# sensors.net
KiCad netlist of a schematic drawn in Altium Designer
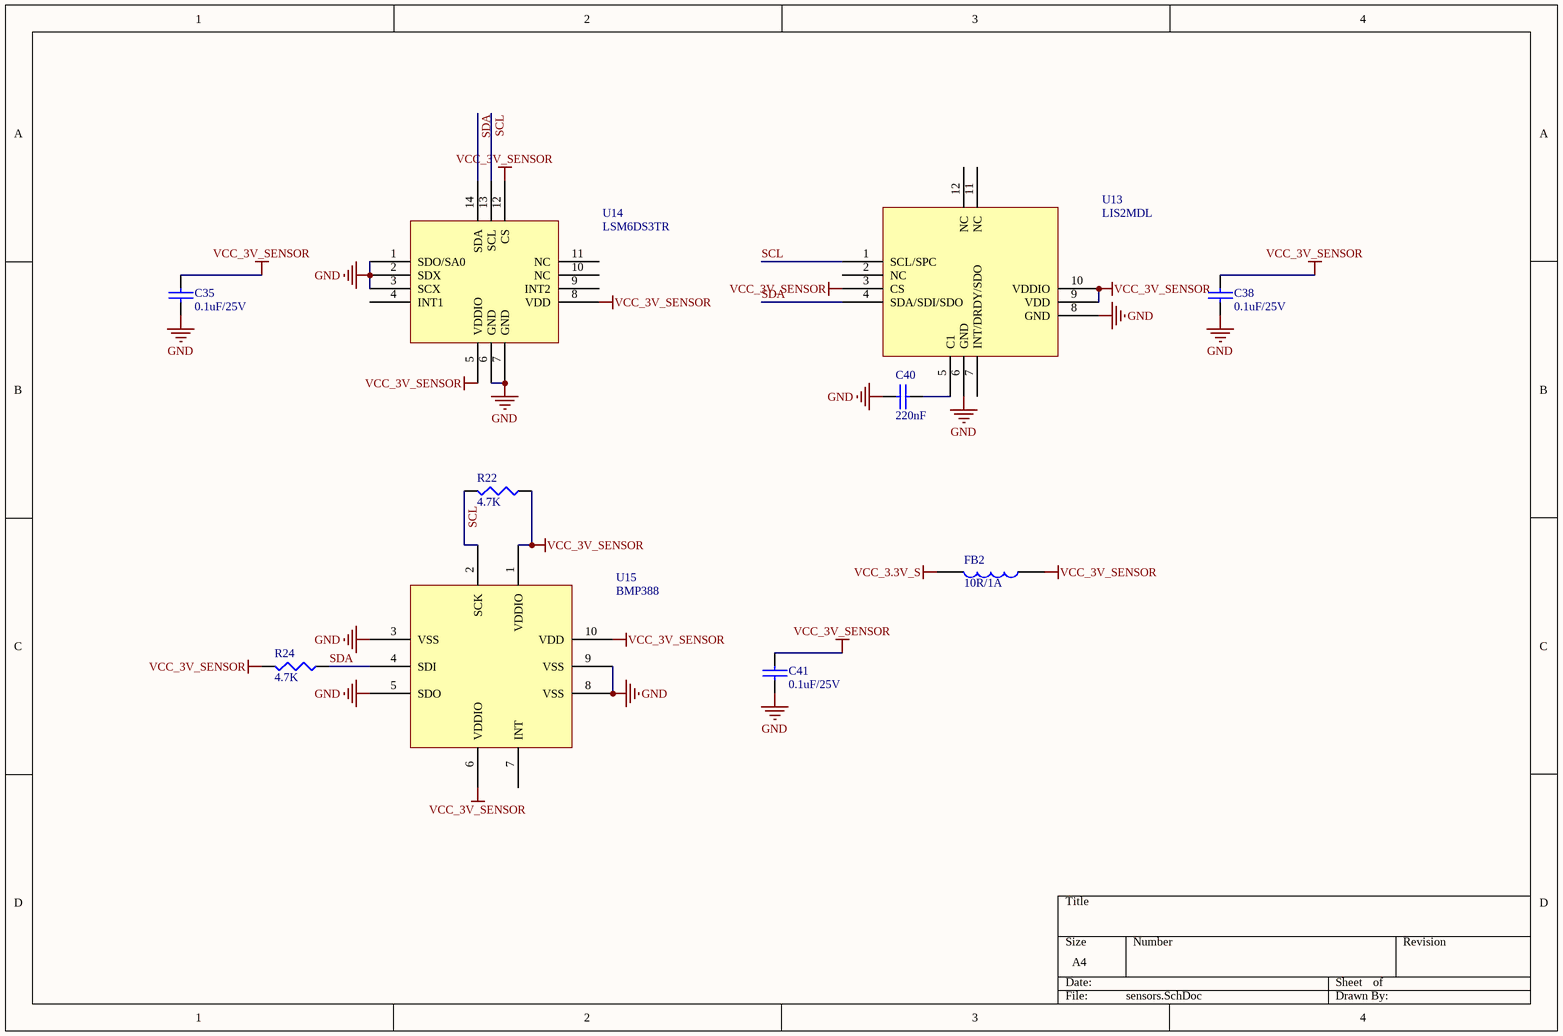
[diagram p0: sensors.SchDoc]

(export (version "E")
  (design (tool "Eeschema 10.0.6"))
  (components
    (comp (ref "C35")
      (value "0.1uF/25V")
      (footprint "0402C")
      (description "Capacitor")
      (libsource (lib "ZWLIntegrated_Library") (part "CAP"))
    )
    (comp (ref "C38")
      (value "0.1uF/25V")
      (footprint "0402C")
      (description "Capacitor")
      (libsource (lib "ZWLIntegrated_Library") (part "CAP"))
    )
    (comp (ref "C40")
      (value "220nF")
      (footprint "0402c")
      (description "Capacitor")
      (libsource (lib "SM") (part "CAP"))
    )
    (comp (ref "C41")
      (value "0.1uF/25V")
      (footprint "0402C")
      (description "Capacitor")
      (libsource (lib "ZWLIntegrated_Library") (part "CAP"))
    )
    (comp (ref "FB2") (value "10R/1A") (footprint "0603R") (libsource (lib "*") (part "INDUCTOR1")))
    (comp (ref "R22")
      (value "4.7K")
      (footprint "0402R")
      (libsource (lib "ZWLIntegrated_Library") (part "RES1"))
    )
    (comp (ref "R24")
      (value "4.7K")
      (footprint "0402R")
      (libsource (lib "ZWLIntegrated_Library") (part "RES1"))
    )
    (comp (ref "U13") (value "LIS2MDL") (footprint "LIS2MDL") (libsource (lib "stm32") (part "LIS2MDL")))
    (comp (ref "U14")
      (value "LSM6DS3TR")
      (footprint "LSM6DS3TR-C")
      (libsource (lib "stm32") (part "LSM6DS3TR"))
    )
    (comp (ref "U15") (value "BMP388") (footprint "BMP388") (libsource (lib "stm32") (part "BMP388")))
  )
  (nets
    (net (code "1") (name "/SCL") (class "Default")
      (node (ref "R22") (pin "2") (pinfunction "2_2") (pintype "passive"))
      (node (ref "U13") (pin "1") (pinfunction "SCL/SPC_1") (pintype "passive"))
      (node (ref "U14") (pin "13") (pinfunction "SCL_13") (pintype "passive"))
      (node (ref "U15") (pin "2") (pinfunction "SCK_2") (pintype "passive"))
    )
    (net (code "2") (name "/SDA") (class "Default")
      (node (ref "R24") (pin "1") (pinfunction "1_1") (pintype "passive"))
      (node (ref "U13") (pin "4") (pinfunction "SDA/SDI/SDO_4") (pintype "passive"))
      (node (ref "U14") (pin "14") (pinfunction "SDA_14") (pintype "passive"))
      (node (ref "U15") (pin "4") (pinfunction "SDI_4") (pintype "passive"))
    )
    (net (code "3") (name "GND") (class "Default")
      (node (ref "C35") (pin "1") (pinfunction "1_1") (pintype "passive"))
      (node (ref "C38") (pin "1") (pinfunction "1_1") (pintype "passive"))
      (node (ref "C40") (pin "2") (pinfunction "2_2") (pintype "passive"))
      (node (ref "C41") (pin "1") (pinfunction "1_1") (pintype "passive"))
      (node (ref "U13") (pin "6") (pinfunction "GND_6") (pintype "passive"))
      (node (ref "U13") (pin "8") (pinfunction "GND_8") (pintype "passive"))
      (node (ref "U14") (pin "1") (pinfunction "SDO/SA0_1") (pintype "passive"))
      (node (ref "U14") (pin "2") (pinfunction "SDX_2") (pintype "passive"))
      (node (ref "U14") (pin "3") (pinfunction "SCX_3") (pintype "passive"))
      (node (ref "U14") (pin "6") (pinfunction "GND_6") (pintype "passive"))
      (node (ref "U14") (pin "7") (pinfunction "GND_7") (pintype "passive"))
      (node (ref "U15") (pin "3") (pinfunction "VSS_3") (pintype "passive"))
      (node (ref "U15") (pin "5") (pinfunction "SDO_5") (pintype "passive"))
      (node (ref "U15") (pin "8") (pinfunction "VSS_8") (pintype "passive"))
      (node (ref "U15") (pin "9") (pinfunction "VSS_9") (pintype "passive"))
    )
    (net (code "4") (name "Net-(U13-C1)") (class "Default")
      (node (ref "C40") (pin "1") (pinfunction "1_1") (pintype "passive"))
      (node (ref "U13") (pin "5") (pinfunction "C1_5") (pintype "passive"))
    )
    (net (code "5") (name "VCC_3.3V_S") (class "Default")
      (node (ref "FB2") (pin "1") (pinfunction "1_1") (pintype "passive"))
    )
    (net (code "6") (name "VCC_3V_SENSOR") (class "Default")
      (node (ref "C35") (pin "2") (pinfunction "2_2") (pintype "passive"))
      (node (ref "C38") (pin "2") (pinfunction "2_2") (pintype "passive"))
      (node (ref "C41") (pin "2") (pinfunction "2_2") (pintype "passive"))
      (node (ref "FB2") (pin "2") (pinfunction "2_2") (pintype "passive"))
      (node (ref "R22") (pin "1") (pinfunction "1_1") (pintype "passive"))
      (node (ref "R24") (pin "2") (pinfunction "2_2") (pintype "passive"))
      (node (ref "U13") (pin "10") (pinfunction "VDDIO_10") (pintype "passive"))
      (node (ref "U13") (pin "3") (pinfunction "CS_3") (pintype "passive"))
      (node (ref "U13") (pin "9") (pinfunction "VDD_9") (pintype "passive"))
      (node (ref "U14") (pin "12") (pinfunction "CS_12") (pintype "passive"))
      (node (ref "U14") (pin "5") (pinfunction "VDDIO_5") (pintype "passive"))
      (node (ref "U14") (pin "8") (pinfunction "VDD_8") (pintype "passive"))
      (node (ref "U15") (pin "1") (pinfunction "VDDIO_1") (pintype "passive"))
      (node (ref "U15") (pin "10") (pinfunction "VDD_10") (pintype "passive"))
      (node (ref "U15") (pin "6") (pinfunction "VDDIO_6") (pintype "passive"))
    )
    (net (code "7") (name "unconnected-(U13-INT{slash}DRDY{slash}SDO-Pad7)") (class "Default")
      (node (ref "U13") (pin "7") (pinfunction "INT/DRDY/SDO_7") (pintype "passive"))
    )
    (net (code "8") (name "unconnected-(U13-NC-Pad2)") (class "Default")
      (node (ref "U13") (pin "2") (pinfunction "NC_2") (pintype "passive"))
    )
    (net (code "9") (name "unconnected-(U13-NC-Pad11)") (class "Default")
      (node (ref "U13") (pin "11") (pinfunction "NC_11") (pintype "passive"))
    )
    (net (code "10") (name "unconnected-(U13-NC-Pad12)") (class "Default")
      (node (ref "U13") (pin "12") (pinfunction "NC_12") (pintype "passive"))
    )
    (net (code "11") (name "unconnected-(U14-INT1-Pad4)") (class "Default")
      (node (ref "U14") (pin "4") (pinfunction "INT1_4") (pintype "passive"))
    )
    (net (code "12") (name "unconnected-(U14-INT2-Pad9)") (class "Default")
      (node (ref "U14") (pin "9") (pinfunction "INT2_9") (pintype "passive"))
    )
    (net (code "13") (name "unconnected-(U14-NC-Pad10)") (class "Default")
      (node (ref "U14") (pin "10") (pinfunction "NC_10") (pintype "passive"))
    )
    (net (code "14") (name "unconnected-(U14-NC-Pad11)") (class "Default")
      (node (ref "U14") (pin "11") (pinfunction "NC_11") (pintype "passive"))
    )
    (net (code "15") (name "unconnected-(U15-INT-Pad7)") (class "Default")
      (node (ref "U15") (pin "7") (pinfunction "INT_7") (pintype "passive"))
    )
  )
)
